# MAX14870_Frontend.net
KiCad netlist of a schematic drawn in Altium Designer
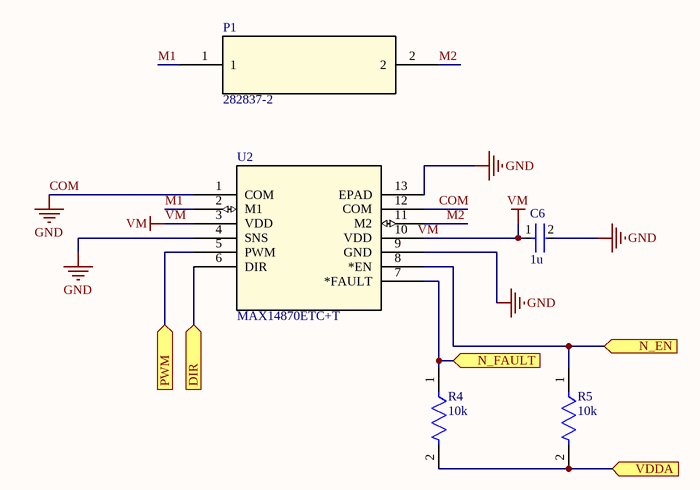
[diagram p0: MAX14870_Frontend.SchDoc]

(export (version "E")
  (design (tool "Eeschema 10.0.6"))
  (components
    (comp (ref "C6")
      (value "1u")
      (footprint "FP-0603-L_1_6_0_15-W_0_8-IPC_C")
      (description "Ceramic Capacitor General Use 1uF ±10% 50V X7R 0603")
      (fields (field (name "TOLERANCE") "10%"))
      (libsource (lib "Altium Content Vault") (part "11868f565c42a9108669ba33697ecf6"))
    )
    (comp (ref "P1")
      (value "282837-2")
      (footprint "282837-2_TYC")
      (description "TERMI-BLOK PCB MOUNT 2P")
      (fields (field (name "COPYRIGHT") "Copyright (C) 2025 Ultra Librarian. All rights reserved."))
      (libsource (lib "Nate Fischer") (part "282837-2"))
    )
    (comp (ref "R4")
      (value "10k")
      (footprint "FP-SG73P1J-MFG")
      (description "SG73P1JTTD1002F Res Thick Film 0603 10K Ohm 1% 0.2W(1/5W) ±100ppm/C Pad SMD Automotive T/R")
      (fields (field (name "TOLERANCE") "1%"))
      (libsource (lib "Altium Content Vault") (part "1029c3af85768c4190bb7ad29bc67b5"))
    )
    (comp (ref "R5")
      (value "10k")
      (footprint "FP-SG73P1J-MFG")
      (description "SG73P1JTTD1002F Res Thick Film 0603 10K Ohm 1% 0.2W(1/5W) ±100ppm/C Pad SMD Automotive T/R")
      (fields (field (name "TOLERANCE") "1%"))
      (libsource (lib "Altium Content Vault") (part "1029c3af85768c4190bb7ad29bc67b5"))
    )
    (comp (ref "U2")
      (value "MAX14870ETC+T")
      (footprint "MAX14870ETC&plus_T:21-0664B_MXM")
      (description "Compact 4.5V to 36V Full-Bridge DC Motor Drivers")
      (fields (field (name "COPYRIGHT") "Copyright (C) 2025 Ultra Librarian. All rights reserved."))
      (libsource (lib "MAX14870ETC&plus_T") (part "MAX14870ETC+T"))
    )
  )
  (nets
    (net (code "1") (name "/DIR") (class "Default")
      (node (ref "U2") (pin "6") (pinfunction "DIR_6") (pintype "passive"))
    )
    (net (code "2") (name "/M1") (class "Default")
      (node (ref "P1") (pin "1") (pinfunction "1_1") (pintype "passive"))
      (node (ref "U2") (pin "2") (pinfunction "M1_2") (pintype "bidirectional"))
    )
    (net (code "3") (name "/M2") (class "Default")
      (node (ref "P1") (pin "2") (pinfunction "2_2") (pintype "passive"))
      (node (ref "U2") (pin "11") (pinfunction "M2_11") (pintype "bidirectional"))
    )
    (net (code "4") (name "/N_EN") (class "Default")
      (node (ref "R5") (pin "1") (pinfunction "1_1") (pintype "passive"))
      (node (ref "U2") (pin "8") (pinfunction "*EN_8") (pintype "passive"))
    )
    (net (code "5") (name "/N_FAULT") (class "Default")
      (node (ref "R4") (pin "1") (pinfunction "1_1") (pintype "passive"))
      (node (ref "U2") (pin "7") (pinfunction "*FAULT_7") (pintype "passive"))
    )
    (net (code "6") (name "/PWM") (class "Default")
      (node (ref "U2") (pin "5") (pinfunction "PWM_5") (pintype "passive"))
    )
    (net (code "7") (name "/VDDA") (class "Default")
      (node (ref "R4") (pin "2") (pinfunction "2_2") (pintype "passive"))
      (node (ref "R5") (pin "2") (pinfunction "2_2") (pintype "passive"))
    )
    (net (code "8") (name "GND") (class "Default")
      (node (ref "C6") (pin "2") (pinfunction "2_2") (pintype "passive"))
      (node (ref "U2") (pin "1") (pinfunction "COM_1") (pintype "passive"))
      (node (ref "U2") (pin "12") (pinfunction "COM_12") (pintype "passive"))
      (node (ref "U2") (pin "13") (pinfunction "EPAD_13") (pintype "passive"))
      (node (ref "U2") (pin "4") (pinfunction "SNS_4") (pintype "passive"))
      (node (ref "U2") (pin "9") (pinfunction "GND_9") (pintype "power_in"))
    )
    (net (code "9") (name "VM") (class "Default")
      (node (ref "C6") (pin "1") (pinfunction "1_1") (pintype "passive"))
      (node (ref "U2") (pin "10") (pinfunction "VDD_10") (pintype "power_in"))
      (node (ref "U2") (pin "3") (pinfunction "VDD_3") (pintype "power_in"))
    )
  )
)
